# Power_Management.net
KiCad netlist of a schematic drawn in Altium Designer
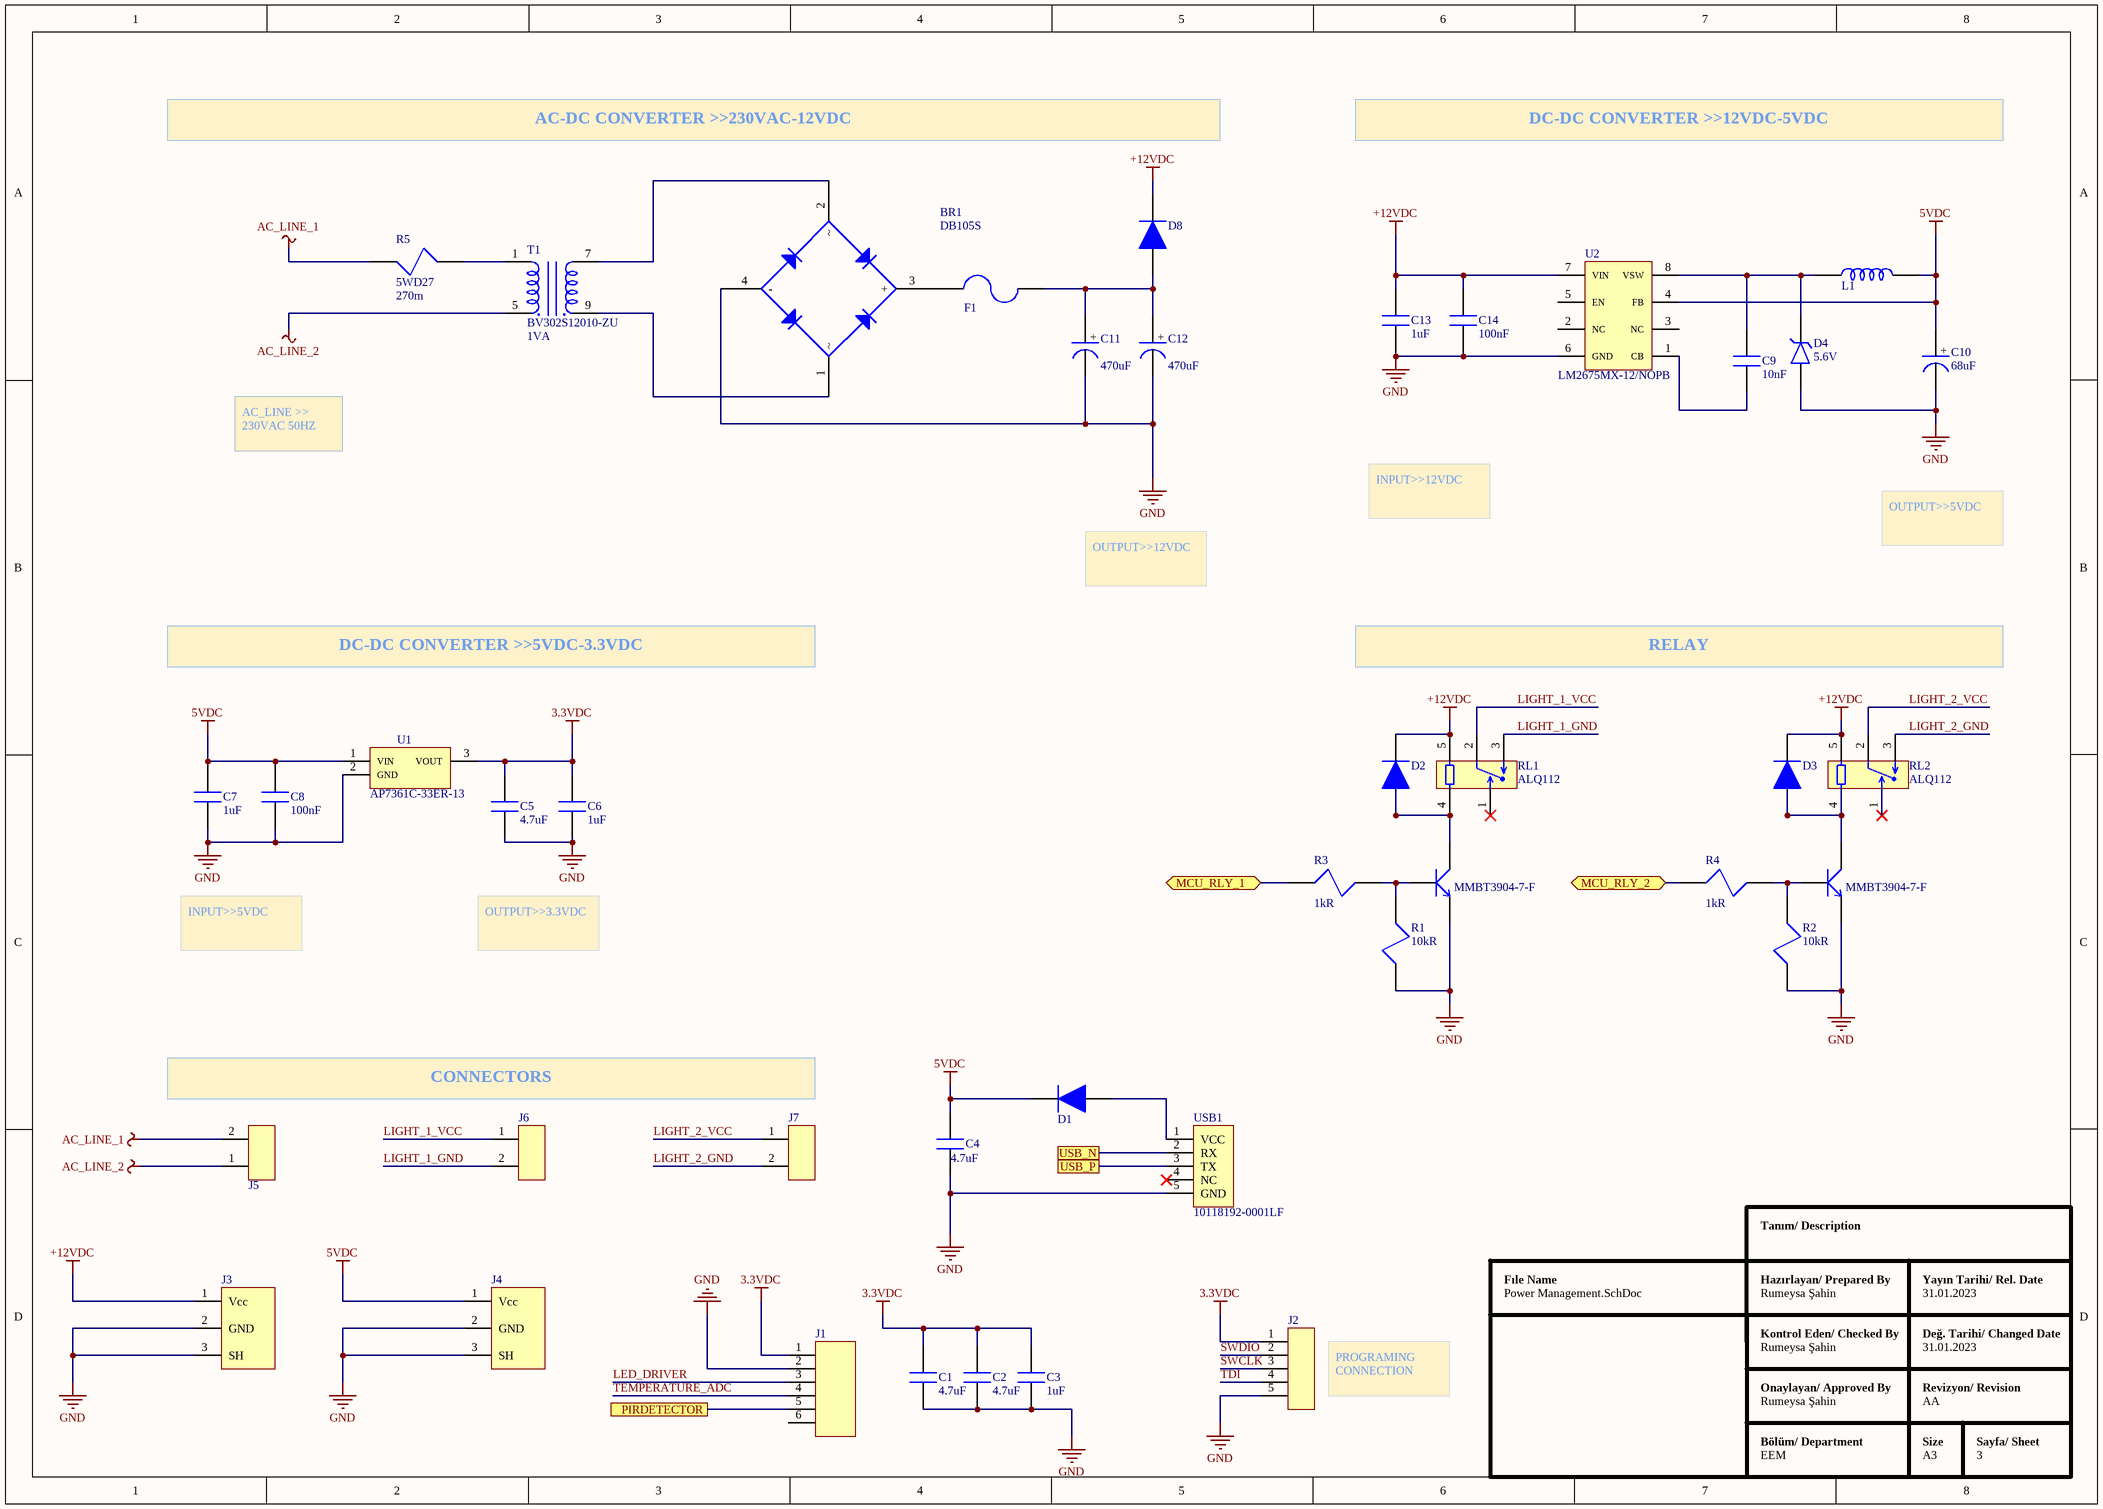
[diagram p0: Power Management.SchDoc]

(export (version "E")
  (design (tool "Eeschema 10.0.6"))
  (components
    (comp (ref "BR1")
      (value "DB105S")
      (footprint "DB105S")
      (description "Bridge Rect 1PHASE 600V 1A Db-s")
      (fields (field (name "MANUFACTURER") "Sangdest Microelectronics"))
      (libsource (lib "Integrated_Library1") (part "DB105S"))
    )
    (comp (ref "C1")
      (value "CL21A475KAQNNNE")
      (footprint "CAP_0805")
      (description "CAP CER 4.7UF 25V X5R 0805")
      (fields
        (field (name "MANUFACTURER") "Samsung")
        (field (name "TOLERANCE") "10%")
        (field (name "CAPACITANCE") "4.7uF")
        (field (name "DESIGNED BY") "Rumeysa Şahin")
      )
      (libsource (lib "Integrated_Library1") (part "CAP CER 4.7uF 0805"))
    )
    (comp (ref "C2")
      (value "CL21A475KAQNNNE")
      (footprint "CAP_0805")
      (description "CAP CER 4.7UF 25V X5R 0805")
      (fields
        (field (name "MANUFACTURER") "Samsung")
        (field (name "TOLERANCE") "10%")
        (field (name "CAPACITANCE") "4.7uF")
        (field (name "DESIGNED BY") "Rumeysa Şahin")
      )
      (libsource (lib "Integrated_Library1") (part "CAP CER 4.7uF 0805"))
    )
    (comp (ref "C3")
      (value "CL21B105KBFNNNE")
      (footprint "CAP_0805")
      (description "CAP CER 1UF 50V X7R 0805")
      (fields
        (field (name "MANUFACTURER") "Samsung")
        (field (name "TOLERANCE") "10%")
        (field (name "CAPACITANCE") "1uF")
        (field (name "DESIGNED BY") "Rumeysa Şahin")
      )
      (libsource (lib "Integrated_Library1") (part "CAP CER 1UF 0805"))
    )
    (comp (ref "C4")
      (value "CL21A475KAQNNNE")
      (footprint "CAP_0805")
      (description "CAP CER 4.7UF 25V X5R 0805")
      (fields
        (field (name "MANUFACTURER") "Samsung")
        (field (name "TOLERANCE") "10%")
        (field (name "CAPACITANCE") "4.7uF")
        (field (name "DESIGNED BY") "Rumeysa Şahin")
      )
      (libsource (lib "Integrated_Library1") (part "CAP CER 4.7uF 0805"))
    )
    (comp (ref "C5")
      (value "CL21A475KAQNNNE")
      (footprint "CAP_0805")
      (description "CAP CER 4.7UF 25V X5R 0805")
      (fields
        (field (name "MANUFACTURER") "Samsung")
        (field (name "TOLERANCE") "10%")
        (field (name "CAPACITANCE") "4.7uF")
        (field (name "DESIGNED BY") "Rumeysa Şahin")
      )
      (libsource (lib "Integrated_Library1") (part "CAP CER 4.7uF 0805"))
    )
    (comp (ref "C6")
      (value "CL21B105KBFNNNE")
      (footprint "CAP_0805")
      (description "CAP CER 1UF 50V X7R 0805")
      (fields
        (field (name "MANUFACTURER") "Samsung")
        (field (name "TOLERANCE") "10%")
        (field (name "CAPACITANCE") "1uF")
        (field (name "DESIGNED BY") "Rumeysa Şahin")
      )
      (libsource (lib "Integrated_Library1") (part "CAP CER 1UF 0805"))
    )
    (comp (ref "C7")
      (value "CL21B105KBFNNNE")
      (footprint "CAP_0805")
      (description "CAP CER 1UF 50V X7R 0805")
      (fields
        (field (name "MANUFACTURER") "Samsung")
        (field (name "TOLERANCE") "10%")
        (field (name "CAPACITANCE") "1uF")
        (field (name "DESIGNED BY") "Rumeysa Şahin")
      )
      (libsource (lib "Integrated_Library1") (part "CAP CER 1UF 0805"))
    )
    (comp (ref "C8")
      (value "C0603C104M5RAC7867")
      (footprint "CAP_0603")
      (description "CAP CER 0.1UF 50V 20% X7R 0603")
      (fields
        (field (name "MANUFACTURER") "KEMET")
        (field (name "MANUFACTURER PART NUMBER") "C0603C104M5RACTU")
        (field (name "CAPACITANCE") "100nF")
        (field (name "DESIGNED BY") "Rumeysa Şahin")
      )
      (libsource (lib "Integrated_Library1") (part "CAP CER 100nF 0603"))
    )
    (comp (ref "C9")
      (value "0603B103K160CT")
      (footprint "CAP_0603")
      (description "Multilayer Ceramic Capacitor, 0.01 F, 10%, X7R, 16 V, 0603 [1608 Metric] RoHS Compliant: Yes")
      (fields
        (field (name "MANUFACTURER") "Walsin Technologies")
        (field (name "TOLERANCE") "10%")
        (field (name "CAPACITANCE") "10nF")
        (field (name "DESIGNED BY") "Rumeysa Şahin")
      )
      (libsource (lib "Integrated_Library1") (part "CAP CER 10nF 0603"))
    )
    (comp (ref "C10")
      (value "EEV686M035A9HAA")
      (footprint "CAP_EEVseries")
      (description "Cap Aluminum Lytic 68uF 35V 20% (6.3 X 7.7mm) SMD 280mA 2000h 105C T/R")
      (fields
        (field (name "MANUFACTURER") "KEMET")
        (field (name "TOLERANCE") "20%")
        (field (name "CAPACITANCE") "68uF")
        (field (name "DESIGNED BY") "Rumeysa Şahin")
      )
      (libsource (lib "Integrated_Library1") (part "CAP ALU 68uF"))
    )
    (comp (ref "C11")
      (value "ESH477M050AH4AA")
      (footprint "ESH477M050AH4AA")
      (description "Cap, 470UF, 50V, Alu Elec, Radial")
      (fields
        (field (name "MANUFACTURER") "KEMET")
        (field (name "TOLERANCE") "20%")
        (field (name "CAPACITANCE") "470uF")
        (field (name "DESIGNED BY") "Rumeysa Şahin")
      )
      (libsource (lib "Integrated_Library1") (part "ESH477M050AH4AA"))
    )
    (comp (ref "C12")
      (value "ESH477M050AH4AA")
      (footprint "ESH477M050AH4AA")
      (description "Cap, 470UF, 50V, Alu Elec, Radial")
      (fields
        (field (name "MANUFACTURER") "KEMET")
        (field (name "TOLERANCE") "20%")
        (field (name "CAPACITANCE") "470uF")
        (field (name "DESIGNED BY") "Rumeysa Şahin")
      )
      (libsource (lib "Integrated_Library1") (part "ESH477M050AH4AA"))
    )
    (comp (ref "C13")
      (value "CL21B105KBFNNNE")
      (footprint "CAP_0805")
      (description "CAP CER 1UF 50V X7R 0805")
      (fields
        (field (name "MANUFACTURER") "Samsung")
        (field (name "TOLERANCE") "10%")
        (field (name "CAPACITANCE") "1uF")
        (field (name "DESIGNED BY") "Rumeysa Şahin")
      )
      (libsource (lib "Integrated_Library1") (part "CAP CER 1UF 0805"))
    )
    (comp (ref "C14")
      (value "CL21B104KBCNNNC")
      (footprint "CAP_0805")
      (description "CAP CER 0.1UF 50V X7R 0805")
      (fields
        (field (name "MANUFACTURER") "Samsung")
        (field (name "TOLERANCE") "10%")
        (field (name "CAPACITANCE") "100nF")
        (field (name "DESIGNED BY") "Rumeysa Şahin")
      )
      (libsource (lib "Integrated_Library1") (part "CAP CER 100nF 0805"))
    )
    (comp (ref "D1")
      (value "1N4148WS")
      (footprint "SOD323F")
      (description "VR=75V IF=150mA Trr=4ns P=200mW")
      (fields
        (field (name "MANUFACTURER") "ON Semiconductor / Fairchild")
        (field (name "DESIGNED BY") "Rumeysa Şahin")
      )
      (libsource (lib "Integrated_Library1") (part "1N4148WS"))
    )
    (comp (ref "D2")
      (value "1N4148WS")
      (footprint "SOD323F")
      (description "VR=75V IF=150mA Trr=4ns P=200mW")
      (fields
        (field (name "MANUFACTURER") "ON Semiconductor / Fairchild")
        (field (name "DESIGNED BY") "Rumeysa Şahin")
      )
      (libsource (lib "Integrated_Library1") (part "1N4148WS"))
    )
    (comp (ref "D3")
      (value "1N4148WS")
      (footprint "SOD323F")
      (description "VR=75V IF=150mA Trr=4ns P=200mW")
      (fields
        (field (name "MANUFACTURER") "ON Semiconductor / Fairchild")
        (field (name "DESIGNED BY") "Rumeysa Şahin")
      )
      (libsource (lib "Integrated_Library1") (part "1N4148WS"))
    )
    (comp (ref "D4")
      (value "1SMB5919BT3G")
      (footprint "SMB")
      (description "Vz=5.6V 5.32V~5.88V Izt=66.9mA")
      (fields
        (field (name "MANUFACTURER") "ON Semiconductor")
        (field (name "TOLERANCE") "5%")
        (field (name "ZENER VOLTAGE") "5.6V")
        (field (name "DESIGNED BY") "Rumeysa Şahin")
      )
      (libsource (lib "Integrated_Library1") (part "1SMB5919BT3G"))
    )
    (comp (ref "D8")
      (value "1N4148WS")
      (footprint "SOD323F")
      (description "VR=75V IF=150mA Trr=4ns P=200mW")
      (fields
        (field (name "MANUFACTURER") "ON Semiconductor / Fairchild")
        (field (name "DESIGNED BY") "Rumeysa Şahin")
      )
      (libsource (lib "Integrated_Library1") (part "1N4148WS"))
    )
    (comp (ref "F1")
      (value "3413.0216.22")
      (footprint "FUSE 3413.0216.22")
      (description "Fuse Chip Fast Acting 1A 32V SMD Solder Pad 1206 Glass T/R VDE/cULus")
      (fields (field (name "MANUFACTURER") "Schurter") (field (name "DESIGNED BY") "Rumeysa Şahin"))
      (libsource (lib "Integrated_Library1") (part "FUSE 3413.0216.22"))
    )
    (comp (ref "J1")
      (value "64800611622")
      (footprint "64800611622")
      (description "Conn, Header, 6POS, 1ROW, 1.5MM;")
      (fields (field (name "MANUFACTURER") "Wurth Electronics") (field (name "DESIGNED BY") "Rumeysa Şahin"))
      (libsource (lib "Integrated_Library1") (part "64800611622_CONN_6PIN"))
    )
    (comp (ref "J2")
      (value "SMH-105-02-L-S")
      (footprint "SMH-105-02-L-S")
      (description ".100 C.L. HORIZONTAL SMT SOCKET")
      (fields (field (name "MANUFACTURER") "Samtec") (field (name "DESIGNED BY") "Rumeysa Şahin"))
      (libsource (lib "Integrated_Library1") (part "SMH-105-02-L-S"))
    )
    (comp (ref "J3")
      (value "PJ-037AH-SMT-TR")
      (footprint "PJ-037AH-SMT-TR")
      (description "2.0 x 6.3 mm, 5.0 A, Horizontal, Surface Mount (SMT), Dc Power Jack Connector")
      (fields (field (name "MANUFACTURER") "CUI") (field (name "DESIGNED BY") "Rumeysa Şahin"))
      (libsource (lib "Integrated_Library1") (part "PJ-037AH-SMT-TR"))
    )
    (comp (ref "J4")
      (value "PJ-037AH-SMT-TR")
      (footprint "PJ-037AH-SMT-TR")
      (description "2.0 x 6.3 mm, 5.0 A, Horizontal, Surface Mount (SMT), Dc Power Jack Connector")
      (fields (field (name "MANUFACTURER") "CUI") (field (name "DESIGNED BY") "Rumeysa Şahin"))
      (libsource (lib "Integrated_Library1") (part "PJ-037AH-SMT-TR"))
    )
    (comp (ref "J5")
      (value "TBP01R1-508-02BE")
      (footprint "TBP01R1-508-02BE")
      (description "2~24 Poles, Pluggable, Receptacle, Horizontal, 5.08 Pitch, Terminal Block Connector")
      (fields (field (name "MANUFACTURER") "CUI") (field (name "DESIGNED BY") "Rumeysa Şahin"))
      (libsource (lib "Integrated_Library1") (part "TBP01R1-508-02BE"))
    )
    (comp (ref "J6")
      (value "TBP01R1-508-02BE")
      (footprint "TBP01R1-508-02BE")
      (description "2~24 Poles, Pluggable, Receptacle, Horizontal, 5.08 Pitch, Terminal Block Connector")
      (fields (field (name "MANUFACTURER") "CUI") (field (name "DESIGNED BY") "Rumeysa Şahin"))
      (libsource (lib "") (part "TBP01R1-508-02BE_1"))
    )
    (comp (ref "J7")
      (value "TBP01R1-508-02BE")
      (footprint "TBP01R1-508-02BE")
      (description "2~24 Poles, Pluggable, Receptacle, Horizontal, 5.08 Pitch, Terminal Block Connector")
      (fields (field (name "MANUFACTURER") "CUI") (field (name "DESIGNED BY") "Rumeysa Şahin"))
      (libsource (lib "") (part "TBP01R1-508-02BE_1"))
    )
    (comp (ref "L1")
      (value "78438335470")
      (footprint "IND_1212")
      (description "Fixed Ind 47UH 390MA 2.3 Ohm SMD")
      (fields
        (field (name "MANUFACTURER") "Wurth Electronics")
        (field (name "TOLERANCE") "30%")
        (field (name "DESIGNED BY") "Rumeysa Şahin")
      )
      (libsource (lib "Integrated_Library1") (part "IND 47uH"))
    )
    (comp (ref "Q1")
      (value "MMBT3904-7-F")
      (footprint "SOT23F")
      (description "NPN Ic=200mA Vceo=40V hfe=100~300 fT=310MHz P=300mW SOT-23")
      (fields (field (name "MANUFACTURER") "Diodes Zetex") (field (name "DESIGNED BY") "Rumeysa Şahin"))
      (libsource (lib "Integrated_Library1") (part "MMBT3904-7-F"))
    )
    (comp (ref "Q2")
      (value "MMBT3904-7-F")
      (footprint "SOT23F")
      (description "NPN Ic=200mA Vceo=40V hfe=100~300 fT=310MHz P=300mW SOT-23")
      (fields (field (name "MANUFACTURER") "Diodes Zetex") (field (name "DESIGNED BY") "Rumeysa Şahin"))
      (libsource (lib "Integrated_Library1") (part "MMBT3904-7-F"))
    )
    (comp (ref "R1")
      (value "RC0603DR-0710KL")
      (footprint "RES_0603")
      (description "Res Thick Film 0603 10K Ohm 0.5% 1/10W ±100ppm/°C Molded SMD Paper T/R")
      (fields
        (field (name "MANUFACTURER") "Yageo")
        (field (name "TOLERANCE") "0.5%")
        (field (name "RESISTANCE") "10kR")
        (field (name "DESIGNED BY") "Rumeysa Şahin")
      )
      (libsource (lib "Integrated_Library1") (part "RES 10K OHM 0603"))
    )
    (comp (ref "R2")
      (value "RC0603DR-0710KL")
      (footprint "RES_0603")
      (description "Res Thick Film 0603 10K Ohm 0.5% 1/10W ±100ppm/°C Molded SMD Paper T/R")
      (fields
        (field (name "MANUFACTURER") "Yageo")
        (field (name "TOLERANCE") "0.5%")
        (field (name "RESISTANCE") "10kR")
        (field (name "DESIGNED BY") "Rumeysa Şahin")
      )
      (libsource (lib "Integrated_Library1") (part "RES 10K OHM 0603"))
    )
    (comp (ref "R3")
      (value "RC0603FR-071KL")
      (footprint "RES_0603")
      (description "Res Thick Film 0603 1K Ohm 1% 1/10W ±100ppm/°C Molded SMD SMD Paper T/R")
      (fields
        (field (name "MANUFACTURER") "Yageo")
        (field (name "TOLERANCE") "1%")
        (field (name "RESISTANCE") "1kR")
        (field (name "DESIGNED BY") "Rumeysa Şahin")
      )
      (libsource (lib "Integrated_Library1") (part "RES 1K OHM 0603"))
    )
    (comp (ref "R4")
      (value "RC0603FR-071KL")
      (footprint "RES_0603")
      (description "Res Thick Film 0603 1K Ohm 1% 1/10W ±100ppm/°C Molded SMD SMD Paper T/R")
      (fields
        (field (name "MANUFACTURER") "Yageo")
        (field (name "TOLERANCE") "1%")
        (field (name "RESISTANCE") "1kR")
        (field (name "DESIGNED BY") "Rumeysa Şahin")
      )
      (libsource (lib "Integrated_Library1") (part "RES 1K OHM 0603"))
    )
    (comp (ref "R5")
      (value "5WD27")
      (footprint "5WD27")
      (description "Resistor 5 Watt Cermet Wirewound Flameproof .27 Ohm 5% Axial Lead")
      (fields
        (field (name "MANUFACTURER") "NTE Electronics")
        (field (name "TOLERANCE") "5%")
        (field (name "RESISTANCE") "270m")
        (field (name "DESIGNED BY") "Rumeysa Şahin")
      )
      (libsource (lib "Integrated_Library1") (part "5WD27"))
    )
    (comp (ref "RL1")
      (value "ALQ112")
      (footprint "ALQ112")
      (description "RELAY GEN PURPOSE SPDT 10A 12V")
      (fields (field (name "MANUFACTURER") "Panasonic"))
      (libsource (lib "Integrated_Library1") (part "ALQ112"))
    )
    (comp (ref "RL2")
      (value "ALQ112")
      (footprint "ALQ112")
      (description "RELAY GEN PURPOSE SPDT 10A 12V")
      (fields (field (name "MANUFACTURER") "Panasonic"))
      (libsource (lib "Integrated_Library1") (part "ALQ112"))
    )
    (comp (ref "T1")
      (value "BV302S12010-ZU")
      (footprint "BV302S12010-ZU - duplicate")
      (description "PWR XFMR LAMINATED 1VA TH")
      (fields (field (name "MANUFACTURER") "Zettler Magnetics") (field (name "RATED POWER") "1VA"))
      (libsource (lib "Integrated_Library1") (part "BV302S12010-ZU"))
    )
    (comp (ref "U1")
      (value "AP7361C-33ER-13")
      (footprint "AP7361C-33ER-13")
      (description "1A Low Dropout Adjustable And Fixed-mode Regulator With Enable")
      (fields (field (name "MANUFACTURER") "Diodes") (field (name "DESIGNED BY") "Rumeysa Şahin"))
      (libsource (lib "Integrated_Library1") (part "AP7361C-33ER-13"))
    )
    (comp (ref "U2")
      (value "LM2675MX-12/NOPB")
      (footprint "SOIC-8")
      (description "SIMPLE SWITCHER® 6.5V to 40V, 1A Low Component Count Step-Down Regulator 8-SOIC -40 to 125")
      (fields (field (name "MANUFACTURER") "TI National Semiconductor"))
      (libsource (lib "Integrated_Library1") (part "LM2675MX-12/NOPB"))
    )
    (comp (ref "USB1")
      (value "10118192-0001LF")
      (footprint "MICRO B USB")
      (description "CONN USB MICRO B RECPT SMT R/A")
      (fields (field (name "MANUFACTURER") "Amphenol ICC / FCI") (field (name "DESIGNED BY") "Rumeysa Şahin"))
      (libsource (lib "Integrated_Library1") (part "MICRO B USB CONNECTOR"))
    )
  )
  (nets
    (net (code "1") (name "+12VDC") (class "Default")
      (node (ref "C13") (pin "2") (pinfunction "2_2") (pintype "passive"))
      (node (ref "C14") (pin "2") (pinfunction "2_2") (pintype "passive"))
      (node (ref "D2") (pin "1") (pinfunction "1_1") (pintype "power_in"))
      (node (ref "D3") (pin "1") (pinfunction "1_1") (pintype "power_in"))
      (node (ref "D8") (pin "1") (pinfunction "1_1") (pintype "power_in"))
      (node (ref "J3") (pin "1") (pinfunction "Vcc_1") (pintype "power_in"))
      (node (ref "RL1") (pin "5") (pinfunction "5_5") (pintype "passive"))
      (node (ref "RL2") (pin "5") (pinfunction "5_5") (pintype "passive"))
      (node (ref "U2") (pin "7") (pinfunction "VIN_7") (pintype "passive"))
    )
    (net (code "2") (name "/LED_DRIVER") (class "Default") (node (ref "J1") (pin "3") (pintype "power_in")))
    (net (code "3") (name "/LIGHT_1_GND") (class "Default")
      (node (ref "J6") (pin "2") (pinfunction "2_2") (pintype "power_in"))
      (node (ref "RL1") (pin "3") (pinfunction "3_3") (pintype "passive"))
    )
    (net (code "4") (name "/LIGHT_1_VCC") (class "Default")
      (node (ref "J6") (pin "1") (pinfunction "1_1") (pintype "power_in"))
      (node (ref "RL1") (pin "2") (pinfunction "2_2") (pintype "passive"))
    )
    (net (code "5") (name "/LIGHT_2_GND") (class "Default")
      (node (ref "J7") (pin "2") (pinfunction "2_2") (pintype "power_in"))
      (node (ref "RL2") (pin "3") (pinfunction "3_3") (pintype "passive"))
    )
    (net (code "6") (name "/LIGHT_2_VCC") (class "Default")
      (node (ref "J7") (pin "1") (pinfunction "1_1") (pintype "power_in"))
      (node (ref "RL2") (pin "2") (pinfunction "2_2") (pintype "passive"))
    )
    (net (code "7") (name "/MCU_RLY_1") (class "Default")
      (node (ref "R3") (pin "2") (pinfunction "2_2") (pintype "passive"))
    )
    (net (code "8") (name "/MCU_RLY_2") (class "Default")
      (node (ref "R4") (pin "2") (pinfunction "2_2") (pintype "passive"))
    )
    (net (code "9") (name "/PIRDETECTOR") (class "Default") (node (ref "J1") (pin "5") (pintype "power_in")))
    (net (code "10") (name "/SWCLK") (class "Default")
      (node (ref "J2") (pin "3") (pinfunction "3_3") (pintype "power_in"))
    )
    (net (code "11") (name "/SWDIO") (class "Default")
      (node (ref "J2") (pin "2") (pinfunction "2_2") (pintype "power_in"))
    )
    (net (code "12") (name "/TDI") (class "Default")
      (node (ref "J2") (pin "4") (pinfunction "4_4") (pintype "power_in"))
    )
    (net (code "13") (name "/TEMPERATURE_ADC") (class "Default")
      (node (ref "J1") (pin "4") (pintype "power_in"))
    )
    (net (code "14") (name "/USB_N") (class "Default")
      (node (ref "USB1") (pin "2") (pinfunction "RX_2") (pintype "power_in"))
    )
    (net (code "15") (name "/USB_P") (class "Default")
      (node (ref "USB1") (pin "3") (pinfunction "TX_3") (pintype "power_in"))
    )
    (net (code "16") (name "3.3VDC") (class "Default")
      (node (ref "C1") (pin "2") (pinfunction "2_2") (pintype "passive"))
      (node (ref "C2") (pin "2") (pinfunction "2_2") (pintype "passive"))
      (node (ref "C3") (pin "2") (pinfunction "2_2") (pintype "passive"))
      (node (ref "C5") (pin "2") (pinfunction "2_2") (pintype "passive"))
      (node (ref "C6") (pin "2") (pinfunction "2_2") (pintype "passive"))
      (node (ref "J1") (pin "1") (pintype "power_in"))
      (node (ref "J2") (pin "1") (pinfunction "1_1") (pintype "power_in"))
      (node (ref "U1") (pin "3") (pinfunction "VOUT_3") (pintype "passive"))
    )
    (net (code "17") (name "5VDC") (class "Default")
      (node (ref "C10") (pin "1") (pinfunction "1_1") (pintype "passive"))
      (node (ref "C4") (pin "2") (pinfunction "2_2") (pintype "passive"))
      (node (ref "C7") (pin "2") (pinfunction "2_2") (pintype "passive"))
      (node (ref "C8") (pin "2") (pinfunction "2_2") (pintype "passive"))
      (node (ref "D1") (pin "1") (pinfunction "1_1") (pintype "power_in"))
      (node (ref "J4") (pin "1") (pinfunction "Vcc_1") (pintype "power_in"))
      (node (ref "L1") (pin "2") (pinfunction "2_2") (pintype "passive"))
      (node (ref "U1") (pin "1") (pinfunction "VIN_1") (pintype "passive"))
      (node (ref "U2") (pin "4") (pinfunction "FB_4") (pintype "passive"))
    )
    (net (code "18") (name "AC_LINE_1") (class "Default")
      (node (ref "J5") (pin "2") (pinfunction "2_2") (pintype "power_in"))
      (node (ref "R5") (pin "1") (pintype "passive"))
    )
    (net (code "19") (name "AC_LINE_2") (class "Default")
      (node (ref "J5") (pin "1") (pinfunction "1_1") (pintype "power_in"))
      (node (ref "T1") (pin "5") (pinfunction "2_5") (pintype "passive"))
    )
    (net (code "20") (name "GND") (class "Default")
      (node (ref "BR1") (pin "4") (pinfunction "-_4") (pintype "passive"))
      (node (ref "C1") (pin "1") (pinfunction "1_1") (pintype "passive"))
      (node (ref "C10") (pin "2") (pinfunction "2_2") (pintype "passive"))
      (node (ref "C11") (pin "2") (pinfunction "2_2") (pintype "passive"))
      (node (ref "C12") (pin "2") (pinfunction "2_2") (pintype "passive"))
      (node (ref "C13") (pin "1") (pinfunction "1_1") (pintype "passive"))
      (node (ref "C14") (pin "1") (pinfunction "1_1") (pintype "passive"))
      (node (ref "C2") (pin "1") (pinfunction "1_1") (pintype "passive"))
      (node (ref "C3") (pin "1") (pinfunction "1_1") (pintype "passive"))
      (node (ref "C4") (pin "1") (pinfunction "1_1") (pintype "passive"))
      (node (ref "C5") (pin "1") (pinfunction "1_1") (pintype "passive"))
      (node (ref "C6") (pin "1") (pinfunction "1_1") (pintype "passive"))
      (node (ref "C7") (pin "1") (pinfunction "1_1") (pintype "passive"))
      (node (ref "C8") (pin "1") (pinfunction "1_1") (pintype "passive"))
      (node (ref "D4") (pin "A") (pinfunction "A_A") (pintype "passive"))
      (node (ref "J1") (pin "2") (pintype "power_in"))
      (node (ref "J2") (pin "5") (pinfunction "5_5") (pintype "power_in"))
      (node (ref "J3") (pin "2") (pinfunction "GND_2") (pintype "power_in"))
      (node (ref "J3") (pin "3") (pinfunction "SH_3") (pintype "power_in"))
      (node (ref "J4") (pin "2") (pinfunction "GND_2") (pintype "power_in"))
      (node (ref "J4") (pin "3") (pinfunction "SH_3") (pintype "power_in"))
      (node (ref "Q1") (pin "2") (pinfunction "E_2") (pintype "power_in"))
      (node (ref "Q2") (pin "2") (pinfunction "E_2") (pintype "power_in"))
      (node (ref "R1") (pin "2") (pinfunction "2_2") (pintype "passive"))
      (node (ref "R2") (pin "2") (pinfunction "2_2") (pintype "passive"))
      (node (ref "U1") (pin "2") (pinfunction "GND_2") (pintype "passive"))
      (node (ref "U2") (pin "6") (pinfunction "GND_6") (pintype "passive"))
      (node (ref "USB1") (pin "5") (pinfunction "GND_5") (pintype "power_in"))
    )
    (net (code "21") (name "Net-(BR1-+)") (class "Default")
      (node (ref "BR1") (pin "3") (pinfunction "+_3") (pintype "passive"))
      (node (ref "F1") (pin "1") (pinfunction "1_1") (pintype "passive"))
    )
    (net (code "22") (name "Net-(C11-Pad1)") (class "Default")
      (node (ref "C11") (pin "1") (pinfunction "1_1") (pintype "passive"))
      (node (ref "C12") (pin "1") (pinfunction "1_1") (pintype "passive"))
      (node (ref "D8") (pin "2") (pinfunction "2_2") (pintype "power_in"))
      (node (ref "F1") (pin "2") (pinfunction "2_2") (pintype "passive"))
    )
    (net (code "23") (name "Net-(Q1-B)") (class "Default")
      (node (ref "Q1") (pin "1") (pinfunction "B_1") (pintype "power_in"))
      (node (ref "R1") (pin "1") (pintype "passive"))
      (node (ref "R3") (pin "1") (pintype "passive"))
    )
    (net (code "24") (name "Net-(Q1-C)") (class "Default")
      (node (ref "D2") (pin "2") (pinfunction "2_2") (pintype "power_in"))
      (node (ref "Q1") (pin "3") (pinfunction "C_3") (pintype "power_in"))
      (node (ref "RL1") (pin "4") (pinfunction "4_4") (pintype "passive"))
    )
    (net (code "25") (name "Net-(Q2-B)") (class "Default")
      (node (ref "Q2") (pin "1") (pinfunction "B_1") (pintype "power_in"))
      (node (ref "R2") (pin "1") (pintype "passive"))
      (node (ref "R4") (pin "1") (pintype "passive"))
    )
    (net (code "26") (name "Net-(Q2-C)") (class "Default")
      (node (ref "D3") (pin "2") (pinfunction "2_2") (pintype "power_in"))
      (node (ref "Q2") (pin "3") (pinfunction "C_3") (pintype "power_in"))
      (node (ref "RL2") (pin "4") (pinfunction "4_4") (pintype "passive"))
    )
    (net (code "27") (name "Net-(R5-Pad2)") (class "Default")
      (node (ref "R5") (pin "2") (pinfunction "2_2") (pintype "passive"))
      (node (ref "T1") (pin "1") (pinfunction "1_1") (pintype "passive"))
    )
    (net (code "28") (name "Net-(T1-3)") (class "Default")
      (node (ref "BR1") (pin "2") (pinfunction "~_2") (pintype "passive"))
      (node (ref "T1") (pin "7") (pinfunction "3_7") (pintype "passive"))
    )
    (net (code "29") (name "Net-(T1-4)") (class "Default")
      (node (ref "BR1") (pin "1") (pinfunction "~_1") (pintype "passive"))
      (node (ref "T1") (pin "9") (pinfunction "4_9") (pintype "passive"))
    )
    (net (code "30") (name "Net-(U2-CB)") (class "Default")
      (node (ref "C9") (pin "1") (pinfunction "1_1") (pintype "passive"))
      (node (ref "U2") (pin "1") (pinfunction "CB_1") (pintype "passive"))
    )
    (net (code "31") (name "Net-(U2-VSW)") (class "Default")
      (node (ref "C9") (pin "2") (pinfunction "2_2") (pintype "passive"))
      (node (ref "D4") (pin "C") (pinfunction "C_C") (pintype "passive"))
      (node (ref "L1") (pin "1") (pinfunction "1_1") (pintype "passive"))
      (node (ref "U2") (pin "8") (pinfunction "VSW_8") (pintype "passive"))
    )
    (net (code "32") (name "Net-(USB1-VCC)") (class "Default")
      (node (ref "D1") (pin "2") (pinfunction "2_2") (pintype "power_in"))
      (node (ref "USB1") (pin "1") (pinfunction "VCC_1") (pintype "power_in"))
    )
    (net (code "33") (name "unconnected-(J1-Pad6)") (class "Default")
      (node (ref "J1") (pin "6") (pintype "power_in"))
    )
    (net (code "34") (name "unconnected-(RL1-Pad1)") (class "Default")
      (node (ref "RL1") (pin "1") (pinfunction "1_1") (pintype "passive+no_connect"))
    )
    (net (code "35") (name "unconnected-(RL2-Pad1)") (class "Default")
      (node (ref "RL2") (pin "1") (pinfunction "1_1") (pintype "passive+no_connect"))
    )
    (net (code "36") (name "unconnected-(U2-EN-Pad5)") (class "Default")
      (node (ref "U2") (pin "5") (pinfunction "EN_5") (pintype "passive"))
    )
    (net (code "37") (name "unconnected-(U2-NC-Pad2)") (class "Default")
      (node (ref "U2") (pin "2") (pinfunction "NC_2") (pintype "passive"))
    )
    (net (code "38") (name "unconnected-(U2-NC-Pad3)") (class "Default")
      (node (ref "U2") (pin "3") (pinfunction "NC_3") (pintype "passive"))
    )
    (net (code "39") (name "unconnected-(USB1-NC-Pad4)") (class "Default")
      (node (ref "USB1") (pin "4") (pinfunction "NC_4") (pintype "power_in+no_connect"))
    )
  )
)
